# VQFN-16_Breakout.net
KiCad netlist of a schematic drawn in EAGLE
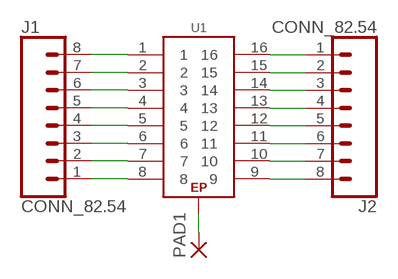
[diagram p0: schematic, sheet 1]

(export (version "E")
  (design (tool "Eeschema 10.0.6"))
  (components
    (comp (ref "J1")
      (value "CONN_82.54")
      (footprint "eagle-import:1X08")
      (libsource (lib "eagle-import") (part "CONN_82.54"))
    )
    (comp (ref "J2")
      (value "CONN_82.54")
      (footprint "eagle-import:1X08")
      (libsource (lib "eagle-import") (part "CONN_82.54"))
    )
    (comp (ref "PAD1")
      (value "SMD2")
      (footprint "eagle-import:SMD1,27-2,54")
      (fields (field (name "MPN") "DNP"))
      (libsource (lib "eagle-import") (part "SMD2"))
    )
    (comp (ref "U1")
      (value "GEN_16_EPVQFN-16")
      (footprint "eagle-import:VQFN-16")
      (libsource (lib "eagle-import") (part "GEN_16_EPVQFN-16"))
    )
  )
  (nets
    (net (code "1") (name "Net-(J1-Pad1)") (class "Default")
      (node (ref "J1") (pin "1") (pinfunction "1_1") (pintype "passive"))
      (node (ref "U1") (pin "8") (pinfunction "8_8") (pintype "bidirectional"))
    )
    (net (code "2") (name "Net-(J1-Pad2)") (class "Default")
      (node (ref "J1") (pin "2") (pinfunction "2_2") (pintype "passive"))
      (node (ref "U1") (pin "7") (pinfunction "7_7") (pintype "bidirectional"))
    )
    (net (code "3") (name "Net-(J1-Pad3)") (class "Default")
      (node (ref "J1") (pin "3") (pinfunction "3_3") (pintype "passive"))
      (node (ref "U1") (pin "6") (pinfunction "6_6") (pintype "bidirectional"))
    )
    (net (code "4") (name "Net-(J1-Pad4)") (class "Default")
      (node (ref "J1") (pin "4") (pinfunction "4_4") (pintype "passive"))
      (node (ref "U1") (pin "5") (pinfunction "5_5") (pintype "bidirectional"))
    )
    (net (code "5") (name "Net-(J1-Pad5)") (class "Default")
      (node (ref "J1") (pin "5") (pinfunction "5_5") (pintype "passive"))
      (node (ref "U1") (pin "4") (pinfunction "4_4") (pintype "bidirectional"))
    )
    (net (code "6") (name "Net-(J1-Pad6)") (class "Default")
      (node (ref "J1") (pin "6") (pinfunction "6_6") (pintype "passive"))
      (node (ref "U1") (pin "3") (pinfunction "3_3") (pintype "bidirectional"))
    )
    (net (code "7") (name "Net-(J1-Pad7)") (class "Default")
      (node (ref "J1") (pin "7") (pinfunction "7_7") (pintype "passive"))
      (node (ref "U1") (pin "2") (pinfunction "2_2") (pintype "bidirectional"))
    )
    (net (code "8") (name "Net-(J1-Pad8)") (class "Default")
      (node (ref "J1") (pin "8") (pinfunction "8_8") (pintype "passive"))
      (node (ref "U1") (pin "1") (pinfunction "1_1") (pintype "bidirectional"))
    )
    (net (code "9") (name "Net-(J2-Pad1)") (class "Default")
      (node (ref "J2") (pin "1") (pinfunction "1_1") (pintype "passive"))
      (node (ref "U1") (pin "16") (pinfunction "16_16") (pintype "bidirectional"))
    )
    (net (code "10") (name "Net-(J2-Pad2)") (class "Default")
      (node (ref "J2") (pin "2") (pinfunction "2_2") (pintype "passive"))
      (node (ref "U1") (pin "15") (pinfunction "15_15") (pintype "bidirectional"))
    )
    (net (code "11") (name "Net-(J2-Pad3)") (class "Default")
      (node (ref "J2") (pin "3") (pinfunction "3_3") (pintype "passive"))
      (node (ref "U1") (pin "14") (pinfunction "14_14") (pintype "bidirectional"))
    )
    (net (code "12") (name "Net-(J2-Pad4)") (class "Default")
      (node (ref "J2") (pin "4") (pinfunction "4_4") (pintype "passive"))
      (node (ref "U1") (pin "13") (pinfunction "13_13") (pintype "bidirectional"))
    )
    (net (code "13") (name "Net-(J2-Pad5)") (class "Default")
      (node (ref "J2") (pin "5") (pinfunction "5_5") (pintype "passive"))
      (node (ref "U1") (pin "12") (pinfunction "12_12") (pintype "bidirectional"))
    )
    (net (code "14") (name "Net-(J2-Pad6)") (class "Default")
      (node (ref "J2") (pin "6") (pinfunction "6_6") (pintype "passive"))
      (node (ref "U1") (pin "11") (pinfunction "11_11") (pintype "bidirectional"))
    )
    (net (code "15") (name "Net-(J2-Pad7)") (class "Default")
      (node (ref "J2") (pin "7") (pinfunction "7_7") (pintype "passive"))
      (node (ref "U1") (pin "10") (pinfunction "10_10") (pintype "bidirectional"))
    )
    (net (code "16") (name "Net-(J2-Pad8)") (class "Default")
      (node (ref "J2") (pin "8") (pinfunction "8_8") (pintype "passive"))
      (node (ref "U1") (pin "9") (pinfunction "9_9") (pintype "bidirectional"))
    )
    (net (code "17") (name "Net-(PAD1-P)") (class "Default")
      (node (ref "PAD1") (pin "1") (pinfunction "P_1") (pintype "passive"))
      (node (ref "U1") (pin "EP") (pinfunction "EP_EP") (pintype "passive"))
    )
  )
)
